# PIC18F66J60-1.net
KiCad netlist of a schematic drawn in EAGLE
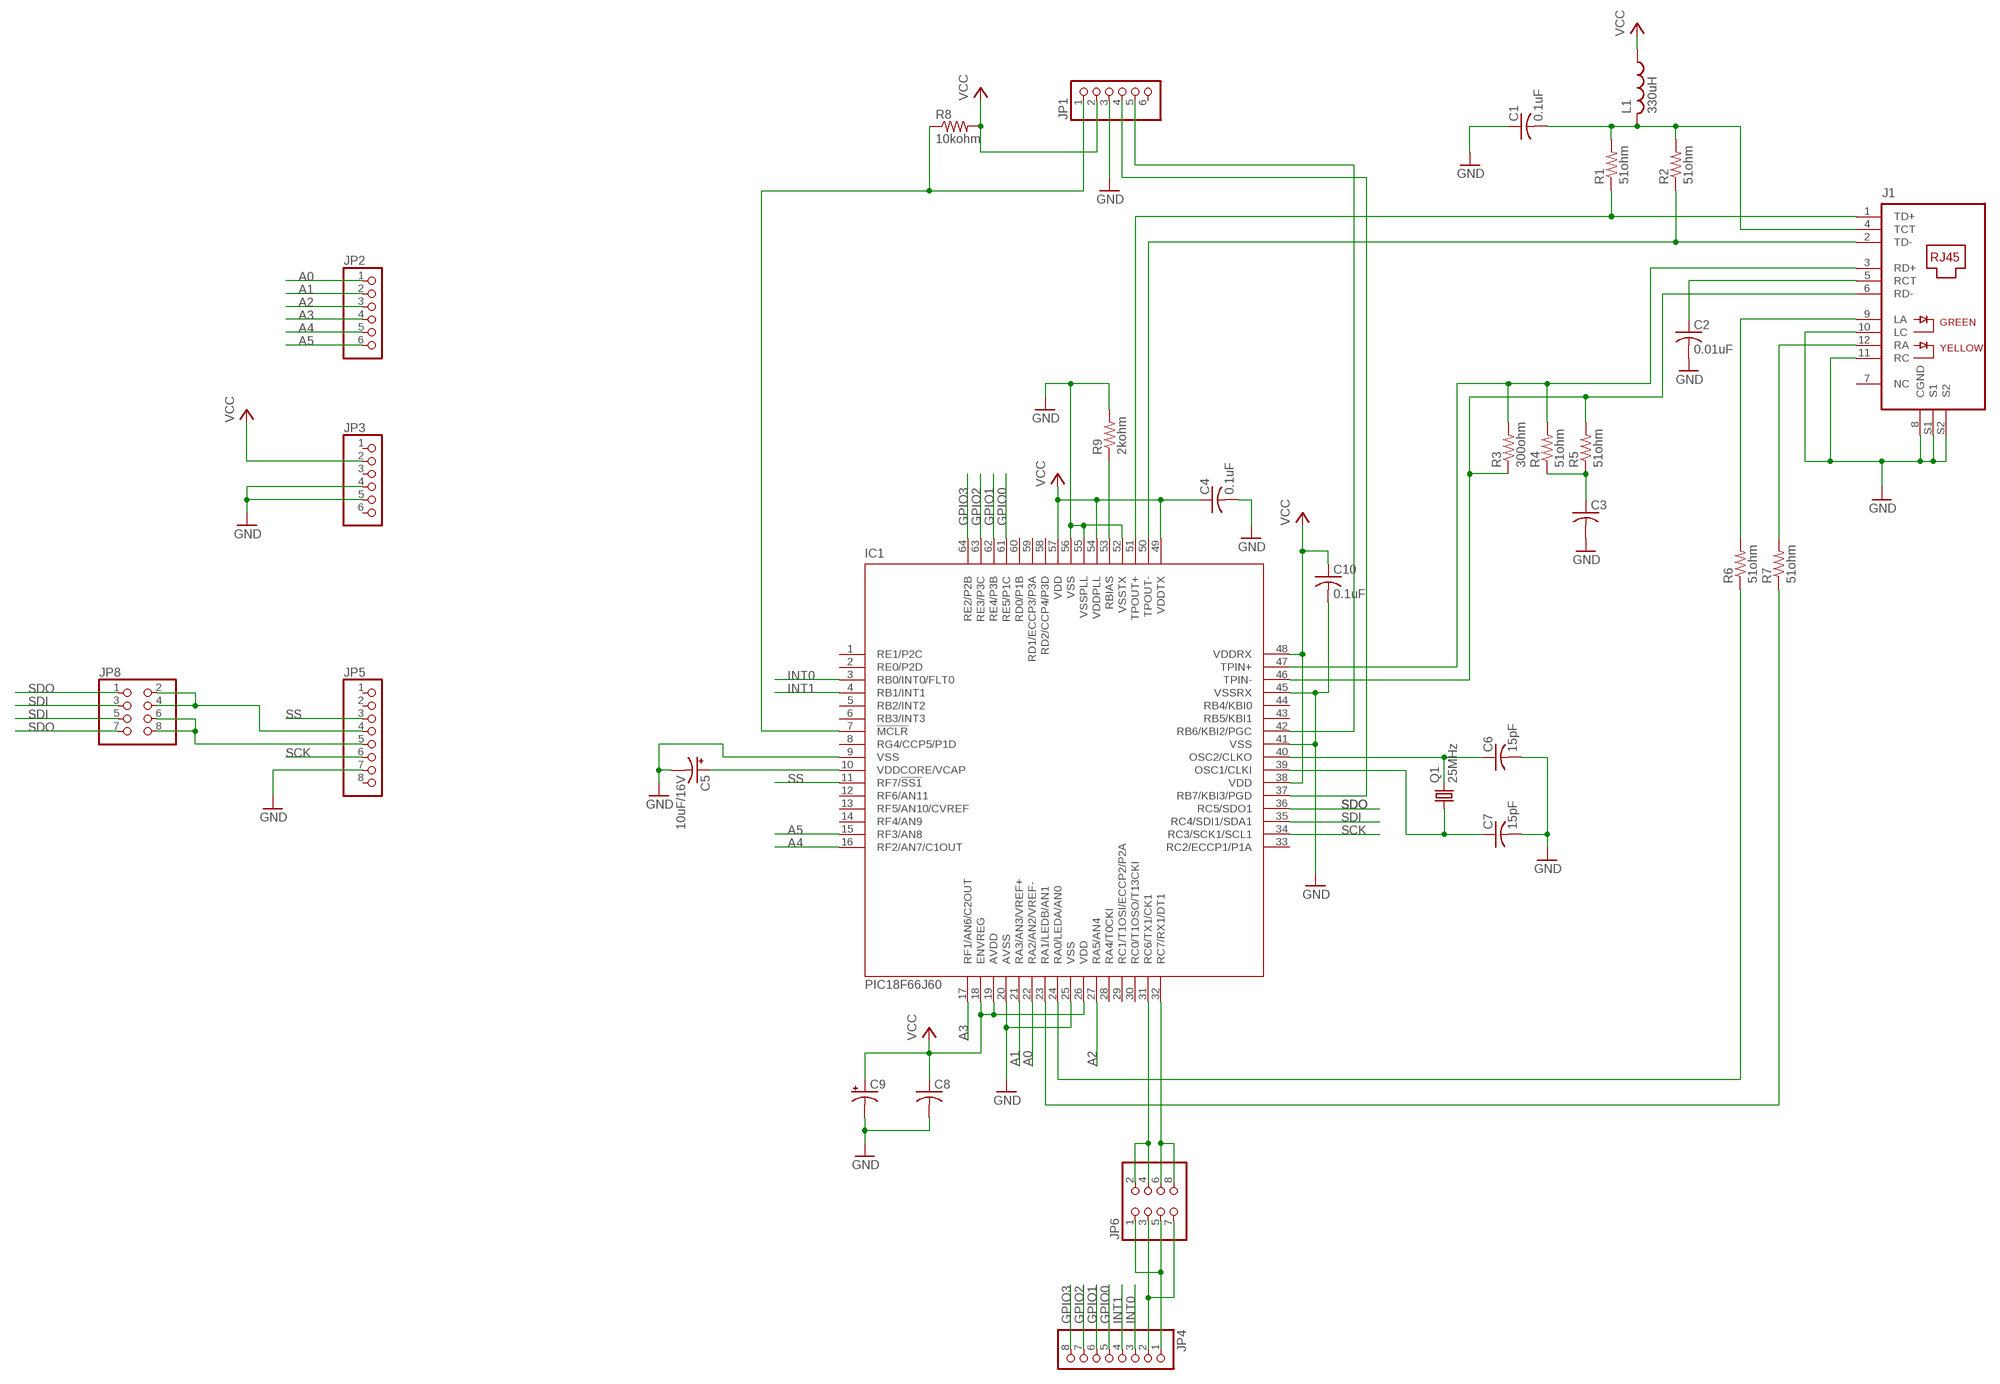
[diagram p0: schematic, sheet 1]

(export (version "E")
  (design (tool "Eeschema 10.0.6"))
  (components
    (comp (ref "C1")
      (value "0.1uF")
      (footprint "eagle-import:C025-040X050")
      (libsource (lib "eagle-import") (part "C-US025-040X050"))
    )
    (comp (ref "C2")
      (value "0.01uF")
      (footprint "eagle-import:C025-040X050")
      (libsource (lib "eagle-import") (part "C-US025-040X050"))
    )
    (comp (ref "C3")
      (value "C-US025-040X050")
      (footprint "eagle-import:C025-040X050")
      (libsource (lib "eagle-import") (part "C-US025-040X050"))
    )
    (comp (ref "C4")
      (value "0.1uF")
      (footprint "eagle-import:C025-040X050")
      (libsource (lib "eagle-import") (part "C-US025-040X050"))
    )
    (comp (ref "C5")
      (value "10uF/16V")
      (footprint "eagle-import:E2,5-7")
      (libsource (lib "eagle-import") (part "CPOL-USE2.5-7"))
    )
    (comp (ref "C6")
      (value "15pF")
      (footprint "eagle-import:C025-040X050")
      (libsource (lib "eagle-import") (part "C-US025-040X050"))
    )
    (comp (ref "C7")
      (value "15pF")
      (footprint "eagle-import:C025-040X050")
      (libsource (lib "eagle-import") (part "C-US025-040X050"))
    )
    (comp (ref "C8")
      (value "C-US025-040X050")
      (footprint "eagle-import:C025-040X050")
      (libsource (lib "eagle-import") (part "C-US025-040X050"))
    )
    (comp (ref "C9")
      (value "CPOL-USE2.5-7")
      (footprint "eagle-import:E2,5-7")
      (libsource (lib "eagle-import") (part "CPOL-USE2.5-7"))
    )
    (comp (ref "C10")
      (value "0.1uF")
      (footprint "eagle-import:C025-040X050")
      (libsource (lib "eagle-import") (part "C-US025-040X050"))
    )
    (comp (ref "IC1")
      (value "PIC18F66J60")
      (footprint "eagle-import:TQFP64-10X10")
      (fields (field (name "MPN") "PIC18F66J60-I/PT"))
      (libsource (lib "eagle-import") (part "PIC18F6J606"))
    )
    (comp (ref "J1")
      (value "J0011")
      (footprint "eagle-import:PJ-J0")
      (libsource (lib "eagle-import") (part "J0011"))
    )
    (comp (ref "JP1")
      (value "PINHD-1X6")
      (footprint "eagle-import:1X06")
      (libsource (lib "eagle-import") (part "PINHD-1X6"))
    )
    (comp (ref "JP2")
      (value "PINHD-1X6")
      (footprint "eagle-import:1X06")
      (libsource (lib "eagle-import") (part "PINHD-1X6"))
    )
    (comp (ref "JP3")
      (value "PINHD-1X6")
      (footprint "eagle-import:1X06")
      (libsource (lib "eagle-import") (part "PINHD-1X6"))
    )
    (comp (ref "JP4")
      (value "PINHD-1X8")
      (footprint "eagle-import:1X08")
      (libsource (lib "eagle-import") (part "PINHD-1X8"))
    )
    (comp (ref "JP5")
      (value "PINHD-1X8")
      (footprint "eagle-import:1X08")
      (libsource (lib "eagle-import") (part "PINHD-1X8"))
    )
    (comp (ref "JP6")
      (value "PINHD-2X4")
      (footprint "eagle-import:2X04")
      (libsource (lib "eagle-import") (part "PINHD-2X4"))
    )
    (comp (ref "JP8")
      (value "PINHD-2X4")
      (footprint "eagle-import:2X04")
      (libsource (lib "eagle-import") (part "PINHD-2X4"))
    )
    (comp (ref "L1")
      (value "330uH")
      (footprint "eagle-import:0204V")
      (libsource (lib "eagle-import") (part "L-US-01"))
    )
    (comp (ref "Q1")
      (value "25MHz")
      (footprint "eagle-import:HC49_S")
      (libsource (lib "eagle-import") (part "CRYSTALHC49S"))
    )
    (comp (ref "R1")
      (value "51ohm")
      (footprint "eagle-import:0204V")
      (libsource (lib "eagle-import") (part "R-US-01"))
    )
    (comp (ref "R2")
      (value "51ohm")
      (footprint "eagle-import:0204V")
      (libsource (lib "eagle-import") (part "R-US-01"))
    )
    (comp (ref "R3")
      (value "300ohm")
      (footprint "eagle-import:0204V")
      (libsource (lib "eagle-import") (part "R-US-01"))
    )
    (comp (ref "R4")
      (value "51ohm")
      (footprint "eagle-import:0204V")
      (libsource (lib "eagle-import") (part "R-US-01"))
    )
    (comp (ref "R5")
      (value "51ohm")
      (footprint "eagle-import:0204V")
      (libsource (lib "eagle-import") (part "R-US-01"))
    )
    (comp (ref "R6")
      (value "51ohm")
      (footprint "eagle-import:0204V")
      (libsource (lib "eagle-import") (part "R-US-01"))
    )
    (comp (ref "R7")
      (value "51ohm")
      (footprint "eagle-import:0204V")
      (libsource (lib "eagle-import") (part "R-US-01"))
    )
    (comp (ref "R8")
      (value "10kohm")
      (footprint "eagle-import:0204V")
      (libsource (lib "eagle-import") (part "R-US-01"))
    )
    (comp (ref "R9")
      (value "2kohm")
      (footprint "eagle-import:0204V")
      (libsource (lib "eagle-import") (part "R-US-01"))
    )
  )
  (nets
    (net (code "1") (name "/A0") (class "Default")
      (node (ref "IC1") (pin "22") (pinfunction "RA2/AN2/VREF-_22") (pintype "bidirectional"))
      (node (ref "JP2") (pin "1") (pinfunction "1_1") (pintype "passive"))
    )
    (net (code "2") (name "/A1") (class "Default")
      (node (ref "IC1") (pin "21") (pinfunction "RA3/AN3/VREF+_21") (pintype "bidirectional"))
      (node (ref "JP2") (pin "2") (pinfunction "2_2") (pintype "passive"))
    )
    (net (code "3") (name "/A2") (class "Default")
      (node (ref "IC1") (pin "27") (pinfunction "RA5/AN4_27") (pintype "bidirectional"))
      (node (ref "JP2") (pin "3") (pinfunction "3_3") (pintype "passive"))
    )
    (net (code "4") (name "/A3") (class "Default")
      (node (ref "IC1") (pin "17") (pinfunction "RF1/AN6/C2OUT_17") (pintype "bidirectional"))
      (node (ref "JP2") (pin "4") (pinfunction "4_4") (pintype "passive"))
    )
    (net (code "5") (name "/A4") (class "Default")
      (node (ref "IC1") (pin "16") (pinfunction "RF2/AN7/C1OUT_16") (pintype "bidirectional"))
      (node (ref "JP2") (pin "5") (pinfunction "5_5") (pintype "passive"))
    )
    (net (code "6") (name "/A5") (class "Default")
      (node (ref "IC1") (pin "15") (pinfunction "RF3/AN8_15") (pintype "bidirectional"))
      (node (ref "JP2") (pin "6") (pinfunction "6_6") (pintype "passive"))
    )
    (net (code "7") (name "/GPIO0") (class "Default")
      (node (ref "IC1") (pin "61") (pinfunction "RE5/P1C_61") (pintype "bidirectional"))
      (node (ref "JP4") (pin "5") (pinfunction "5_5") (pintype "passive"))
    )
    (net (code "8") (name "/GPIO1") (class "Default")
      (node (ref "IC1") (pin "62") (pinfunction "RE4/P3B_62") (pintype "bidirectional"))
      (node (ref "JP4") (pin "6") (pinfunction "6_6") (pintype "passive"))
    )
    (net (code "9") (name "/GPIO2") (class "Default")
      (node (ref "IC1") (pin "63") (pinfunction "RE3/P3C_63") (pintype "bidirectional"))
      (node (ref "JP4") (pin "7") (pinfunction "7_7") (pintype "passive"))
    )
    (net (code "10") (name "/GPIO3") (class "Default")
      (node (ref "IC1") (pin "64") (pinfunction "RE2/P2B_64") (pintype "bidirectional"))
      (node (ref "JP4") (pin "8") (pinfunction "8_8") (pintype "passive"))
    )
    (net (code "11") (name "/INT0") (class "Default")
      (node (ref "IC1") (pin "3") (pinfunction "RB0/INT0/FLT0_3") (pintype "bidirectional"))
      (node (ref "JP4") (pin "3") (pinfunction "3_3") (pintype "passive"))
    )
    (net (code "12") (name "/INT1") (class "Default")
      (node (ref "IC1") (pin "4") (pinfunction "RB1/INT1_4") (pintype "bidirectional"))
      (node (ref "JP4") (pin "4") (pinfunction "4_4") (pintype "passive"))
    )
    (net (code "13") (name "/SCK") (class "Default")
      (node (ref "IC1") (pin "34") (pinfunction "RC3/SCK1/SCL1_34") (pintype "bidirectional"))
      (node (ref "JP5") (pin "6") (pinfunction "6_6") (pintype "passive"))
    )
    (net (code "14") (name "/SDI") (class "Default")
      (node (ref "IC1") (pin "35") (pinfunction "RC4/SDI1/SDA1_35") (pintype "bidirectional"))
      (node (ref "JP8") (pin "3") (pinfunction "3_3") (pintype "passive"))
      (node (ref "JP8") (pin "5") (pinfunction "5_5") (pintype "passive"))
    )
    (net (code "15") (name "/SDO") (class "Default")
      (node (ref "IC1") (pin "36") (pinfunction "RC5/SDO1_36") (pintype "bidirectional"))
      (node (ref "JP8") (pin "1") (pinfunction "1_1") (pintype "passive"))
      (node (ref "JP8") (pin "7") (pinfunction "7_7") (pintype "passive"))
    )
    (net (code "16") (name "/SS") (class "Default")
      (node (ref "IC1") (pin "11") (pinfunction "RF7/~{SS1}_11") (pintype "bidirectional"))
      (node (ref "JP5") (pin "3") (pinfunction "3_3") (pintype "passive"))
    )
    (net (code "17") (name "GND") (class "Default")
      (node (ref "C1") (pin "1") (pinfunction "1_1") (pintype "passive"))
      (node (ref "C10") (pin "2") (pinfunction "2_2") (pintype "passive"))
      (node (ref "C2") (pin "2") (pinfunction "2_2") (pintype "passive"))
      (node (ref "C3") (pin "2") (pinfunction "2_2") (pintype "passive"))
      (node (ref "C4") (pin "2") (pinfunction "2_2") (pintype "passive"))
      (node (ref "C5") (pin "-") (pinfunction "-_-") (pintype "passive"))
      (node (ref "C6") (pin "2") (pinfunction "2_2") (pintype "passive"))
      (node (ref "C7") (pin "2") (pinfunction "2_2") (pintype "passive"))
      (node (ref "C8") (pin "2") (pinfunction "2_2") (pintype "passive"))
      (node (ref "C9") (pin "-") (pinfunction "-_-") (pintype "passive"))
      (node (ref "IC1") (pin "20") (pinfunction "AVSS_20") (pintype "bidirectional"))
      (node (ref "IC1") (pin "25") (pinfunction "VSS_25") (pintype "bidirectional"))
      (node (ref "IC1") (pin "41") (pinfunction "VSS_41") (pintype "bidirectional"))
      (node (ref "IC1") (pin "45") (pinfunction "VSSRX_45") (pintype "bidirectional"))
      (node (ref "IC1") (pin "52") (pinfunction "VSSTX_52") (pintype "bidirectional"))
      (node (ref "IC1") (pin "55") (pinfunction "VSSPLL_55") (pintype "bidirectional"))
      (node (ref "IC1") (pin "56") (pinfunction "VSS_56") (pintype "bidirectional"))
      (node (ref "IC1") (pin "9") (pinfunction "VSS_9") (pintype "bidirectional"))
      (node (ref "J1") (pin "10") (pinfunction "LC_10") (pintype "passive"))
      (node (ref "J1") (pin "11") (pinfunction "RC_11") (pintype "passive"))
      (node (ref "J1") (pin "8") (pinfunction "CGND_8") (pintype "passive"))
      (node (ref "J1") (pin "S1") (pinfunction "S1_S1") (pintype "passive"))
      (node (ref "J1") (pin "S2") (pinfunction "S2_S2") (pintype "passive"))
      (node (ref "JP1") (pin "3") (pinfunction "3_3") (pintype "passive"))
      (node (ref "JP3") (pin "4") (pinfunction "4_4") (pintype "passive"))
      (node (ref "JP3") (pin "5") (pinfunction "5_5") (pintype "passive"))
      (node (ref "JP5") (pin "7") (pinfunction "7_7") (pintype "passive"))
      (node (ref "R9") (pin "2") (pinfunction "2_2") (pintype "passive"))
    )
    (net (code "18") (name "Net-(C3-Pad1)") (class "Default")
      (node (ref "C3") (pin "1") (pinfunction "1_1") (pintype "passive"))
      (node (ref "R4") (pin "1") (pinfunction "1_1") (pintype "passive"))
      (node (ref "R5") (pin "1") (pinfunction "1_1") (pintype "passive"))
    )
    (net (code "19") (name "Net-(IC1-OSC1{slash}CLKI)") (class "Default")
      (node (ref "C7") (pin "1") (pinfunction "1_1") (pintype "passive"))
      (node (ref "IC1") (pin "39") (pinfunction "OSC1/CLKI_39") (pintype "bidirectional"))
      (node (ref "Q1") (pin "1") (pinfunction "1_1") (pintype "passive"))
    )
    (net (code "20") (name "Net-(IC1-OSC2{slash}CLKO)") (class "Default")
      (node (ref "C6") (pin "1") (pinfunction "1_1") (pintype "passive"))
      (node (ref "IC1") (pin "40") (pinfunction "OSC2/CLKO_40") (pintype "bidirectional"))
      (node (ref "Q1") (pin "2") (pinfunction "2_2") (pintype "passive"))
    )
    (net (code "21") (name "Net-(IC1-RA0{slash}LEDA{slash}AN0)") (class "Default")
      (node (ref "IC1") (pin "24") (pinfunction "RA0/LEDA/AN0_24") (pintype "bidirectional"))
      (node (ref "R6") (pin "1") (pinfunction "1_1") (pintype "passive"))
    )
    (net (code "22") (name "Net-(IC1-RA1{slash}LEDB{slash}AN1)") (class "Default")
      (node (ref "IC1") (pin "23") (pinfunction "RA1/LEDB/AN1_23") (pintype "bidirectional"))
      (node (ref "R7") (pin "1") (pinfunction "1_1") (pintype "passive"))
    )
    (net (code "23") (name "Net-(IC1-RB6{slash}KBI2{slash}PGC)") (class "Default")
      (node (ref "IC1") (pin "42") (pinfunction "RB6/KBI2/PGC_42") (pintype "bidirectional"))
      (node (ref "JP1") (pin "5") (pinfunction "5_5") (pintype "passive"))
    )
    (net (code "24") (name "Net-(IC1-RB7{slash}KBI3{slash}PGD)") (class "Default")
      (node (ref "IC1") (pin "37") (pinfunction "RB7/KBI3/PGD_37") (pintype "bidirectional"))
      (node (ref "JP1") (pin "4") (pinfunction "4_4") (pintype "passive"))
    )
    (net (code "25") (name "Net-(IC1-RBIAS)") (class "Default")
      (node (ref "IC1") (pin "53") (pinfunction "RBIAS_53") (pintype "bidirectional"))
      (node (ref "R9") (pin "1") (pinfunction "1_1") (pintype "passive"))
    )
    (net (code "26") (name "Net-(IC1-RC6{slash}TX1{slash}CK1)") (class "Default")
      (node (ref "IC1") (pin "31") (pinfunction "RC6/TX1/CK1_31") (pintype "bidirectional"))
      (node (ref "JP6") (pin "2") (pinfunction "2_2") (pintype "passive"))
      (node (ref "JP6") (pin "4") (pinfunction "4_4") (pintype "passive"))
    )
    (net (code "27") (name "Net-(IC1-RC7{slash}RX1{slash}DT1)") (class "Default")
      (node (ref "IC1") (pin "32") (pinfunction "RC7/RX1/DT1_32") (pintype "bidirectional"))
      (node (ref "JP6") (pin "6") (pinfunction "6_6") (pintype "passive"))
      (node (ref "JP6") (pin "8") (pinfunction "8_8") (pintype "passive"))
    )
    (net (code "28") (name "Net-(IC1-TPIN+)") (class "Default")
      (node (ref "IC1") (pin "47") (pinfunction "TPIN+_47") (pintype "bidirectional"))
      (node (ref "J1") (pin "3") (pinfunction "RD+_3") (pintype "bidirectional"))
      (node (ref "R3") (pin "2") (pinfunction "2_2") (pintype "passive"))
      (node (ref "R4") (pin "2") (pinfunction "2_2") (pintype "passive"))
    )
    (net (code "29") (name "Net-(IC1-TPIN-)") (class "Default")
      (node (ref "IC1") (pin "46") (pinfunction "TPIN-_46") (pintype "bidirectional"))
      (node (ref "J1") (pin "6") (pinfunction "RD-_6") (pintype "bidirectional"))
      (node (ref "R3") (pin "1") (pinfunction "1_1") (pintype "passive"))
      (node (ref "R5") (pin "2") (pinfunction "2_2") (pintype "passive"))
    )
    (net (code "30") (name "Net-(IC1-TPOUT+)") (class "Default")
      (node (ref "IC1") (pin "51") (pinfunction "TPOUT+_51") (pintype "bidirectional"))
      (node (ref "J1") (pin "1") (pinfunction "TD+_1") (pintype "bidirectional"))
      (node (ref "R1") (pin "1") (pinfunction "1_1") (pintype "passive"))
    )
    (net (code "31") (name "Net-(IC1-TPOUT-)") (class "Default")
      (node (ref "IC1") (pin "50") (pinfunction "TPOUT-_50") (pintype "bidirectional"))
      (node (ref "J1") (pin "2") (pinfunction "TD-_2") (pintype "bidirectional"))
      (node (ref "R2") (pin "1") (pinfunction "1_1") (pintype "passive"))
    )
    (net (code "32") (name "Net-(IC1-VDDCORE{slash}VCAP)") (class "Default")
      (node (ref "C5") (pin "+") (pinfunction "+_+") (pintype "passive"))
      (node (ref "IC1") (pin "10") (pinfunction "VDDCORE/VCAP_10") (pintype "bidirectional"))
    )
    (net (code "33") (name "Net-(IC1-~{MCLR})") (class "Default")
      (node (ref "IC1") (pin "7") (pinfunction "~{MCLR}_7") (pintype "bidirectional"))
      (node (ref "JP1") (pin "1") (pinfunction "1_1") (pintype "passive"))
      (node (ref "R8") (pin "1") (pinfunction "1_1") (pintype "passive"))
    )
    (net (code "34") (name "Net-(J1-LA)") (class "Default")
      (node (ref "J1") (pin "9") (pinfunction "LA_9") (pintype "passive"))
      (node (ref "R6") (pin "2") (pinfunction "2_2") (pintype "passive"))
    )
    (net (code "35") (name "Net-(J1-RA)") (class "Default")
      (node (ref "J1") (pin "12") (pinfunction "RA_12") (pintype "passive"))
      (node (ref "R7") (pin "2") (pinfunction "2_2") (pintype "passive"))
    )
    (net (code "36") (name "Net-(J1-RCT)") (class "Default")
      (node (ref "C2") (pin "1") (pinfunction "1_1") (pintype "passive"))
      (node (ref "J1") (pin "5") (pinfunction "RCT_5") (pintype "bidirectional"))
    )
    (net (code "37") (name "Net-(J1-TCT)") (class "Default")
      (node (ref "C1") (pin "2") (pinfunction "2_2") (pintype "passive"))
      (node (ref "J1") (pin "4") (pinfunction "TCT_4") (pintype "bidirectional"))
      (node (ref "L1") (pin "2") (pinfunction "2_2") (pintype "passive"))
      (node (ref "R1") (pin "2") (pinfunction "2_2") (pintype "passive"))
      (node (ref "R2") (pin "2") (pinfunction "2_2") (pintype "passive"))
    )
    (net (code "38") (name "Net-(JP4-Pad1)") (class "Default")
      (node (ref "JP4") (pin "1") (pinfunction "1_1") (pintype "passive"))
      (node (ref "JP6") (pin "1") (pinfunction "1_1") (pintype "passive"))
      (node (ref "JP6") (pin "5") (pinfunction "5_5") (pintype "passive"))
    )
    (net (code "39") (name "Net-(JP4-Pad2)") (class "Default")
      (node (ref "JP4") (pin "2") (pinfunction "2_2") (pintype "passive"))
      (node (ref "JP6") (pin "3") (pinfunction "3_3") (pintype "passive"))
      (node (ref "JP6") (pin "7") (pinfunction "7_7") (pintype "passive"))
    )
    (net (code "40") (name "Net-(JP5-Pad4)") (class "Default")
      (node (ref "JP5") (pin "4") (pinfunction "4_4") (pintype "passive"))
      (node (ref "JP8") (pin "2") (pinfunction "2_2") (pintype "passive"))
      (node (ref "JP8") (pin "4") (pinfunction "4_4") (pintype "passive"))
    )
    (net (code "41") (name "Net-(JP5-Pad5)") (class "Default")
      (node (ref "JP5") (pin "5") (pinfunction "5_5") (pintype "passive"))
      (node (ref "JP8") (pin "6") (pinfunction "6_6") (pintype "passive"))
      (node (ref "JP8") (pin "8") (pinfunction "8_8") (pintype "passive"))
    )
    (net (code "42") (name "VCC") (class "Default")
      (node (ref "C10") (pin "1") (pinfunction "1_1") (pintype "passive"))
      (node (ref "C4") (pin "1") (pinfunction "1_1") (pintype "passive"))
      (node (ref "C8") (pin "1") (pinfunction "1_1") (pintype "passive"))
      (node (ref "C9") (pin "+") (pinfunction "+_+") (pintype "passive"))
      (node (ref "IC1") (pin "18") (pinfunction "ENVREG_18") (pintype "bidirectional"))
      (node (ref "IC1") (pin "19") (pinfunction "AVDD_19") (pintype "bidirectional"))
      (node (ref "IC1") (pin "26") (pinfunction "VDD_26") (pintype "bidirectional"))
      (node (ref "IC1") (pin "38") (pinfunction "VDD_38") (pintype "bidirectional"))
      (node (ref "IC1") (pin "48") (pinfunction "VDDRX_48") (pintype "bidirectional"))
      (node (ref "IC1") (pin "49") (pinfunction "VDDTX_49") (pintype "bidirectional"))
      (node (ref "IC1") (pin "54") (pinfunction "VDDPLL_54") (pintype "bidirectional"))
      (node (ref "IC1") (pin "57") (pinfunction "VDD_57") (pintype "bidirectional"))
      (node (ref "JP1") (pin "2") (pinfunction "2_2") (pintype "passive"))
      (node (ref "JP3") (pin "2") (pinfunction "2_2") (pintype "passive"))
      (node (ref "L1") (pin "1") (pinfunction "1_1") (pintype "passive"))
      (node (ref "R8") (pin "2") (pinfunction "2_2") (pintype "passive"))
    )
    (net (code "43") (name "unconnected-(IC1-RA4{slash}T0CKI-Pad28)") (class "Default")
      (node (ref "IC1") (pin "28") (pinfunction "RA4/T0CKI_28") (pintype "bidirectional"))
    )
    (net (code "44") (name "unconnected-(IC1-RB2{slash}INT2-Pad5)") (class "Default")
      (node (ref "IC1") (pin "5") (pinfunction "RB2/INT2_5") (pintype "bidirectional"))
    )
    (net (code "45") (name "unconnected-(IC1-RB3{slash}INT3-Pad6)") (class "Default")
      (node (ref "IC1") (pin "6") (pinfunction "RB3/INT3_6") (pintype "bidirectional"))
    )
    (net (code "46") (name "unconnected-(IC1-RB4{slash}KBI0-Pad44)") (class "Default")
      (node (ref "IC1") (pin "44") (pinfunction "RB4/KBI0_44") (pintype "bidirectional"))
    )
    (net (code "47") (name "unconnected-(IC1-RB5{slash}KBI1-Pad43)") (class "Default")
      (node (ref "IC1") (pin "43") (pinfunction "RB5/KBI1_43") (pintype "bidirectional"))
    )
    (net (code "48") (name "unconnected-(IC1-RC0{slash}T1OSO{slash}T13CKI-Pad30)") (class "Default")
      (node (ref "IC1") (pin "30") (pinfunction "RC0/T1OSO/T13CKI_30") (pintype "bidirectional"))
    )
    (net (code "49") (name "unconnected-(IC1-RC1{slash}T1OSI{slash}ECCP2{slash}P2A-Pad29)") (class "Default")
      (node (ref "IC1") (pin "29") (pinfunction "RC1/T1OSI/ECCP2/P2A_29") (pintype "bidirectional"))
    )
    (net (code "50") (name "unconnected-(IC1-RC2{slash}ECCP1{slash}P1A-Pad33)") (class "Default")
      (node (ref "IC1") (pin "33") (pinfunction "RC2/ECCP1/P1A_33") (pintype "bidirectional"))
    )
    (net (code "51") (name "unconnected-(IC1-RD0{slash}P1B-Pad60)") (class "Default")
      (node (ref "IC1") (pin "60") (pinfunction "RD0/P1B_60") (pintype "bidirectional"))
    )
    (net (code "52") (name "unconnected-(IC1-RD1{slash}ECCP3{slash}P3A-Pad59)") (class "Default")
      (node (ref "IC1") (pin "59") (pinfunction "RD1/ECCP3/P3A_59") (pintype "bidirectional"))
    )
    (net (code "53") (name "unconnected-(IC1-RD2{slash}CCP4{slash}P3D-Pad58)") (class "Default")
      (node (ref "IC1") (pin "58") (pinfunction "RD2/CCP4/P3D_58") (pintype "bidirectional"))
    )
    (net (code "54") (name "unconnected-(IC1-RE0{slash}P2D-Pad2)") (class "Default")
      (node (ref "IC1") (pin "2") (pinfunction "RE0/P2D_2") (pintype "bidirectional"))
    )
    (net (code "55") (name "unconnected-(IC1-RE1{slash}P2C-Pad1)") (class "Default")
      (node (ref "IC1") (pin "1") (pinfunction "RE1/P2C_1") (pintype "bidirectional"))
    )
    (net (code "56") (name "unconnected-(IC1-RF4{slash}AN9-Pad14)") (class "Default")
      (node (ref "IC1") (pin "14") (pinfunction "RF4/AN9_14") (pintype "bidirectional"))
    )
    (net (code "57") (name "unconnected-(IC1-RF5{slash}AN10{slash}CVREF-Pad13)") (class "Default")
      (node (ref "IC1") (pin "13") (pinfunction "RF5/AN10/CVREF_13") (pintype "bidirectional"))
    )
    (net (code "58") (name "unconnected-(IC1-RF6{slash}AN11-Pad12)") (class "Default")
      (node (ref "IC1") (pin "12") (pinfunction "RF6/AN11_12") (pintype "bidirectional"))
    )
    (net (code "59") (name "unconnected-(IC1-RG4{slash}CCP5{slash}P1D-Pad8)") (class "Default")
      (node (ref "IC1") (pin "8") (pinfunction "RG4/CCP5/P1D_8") (pintype "bidirectional"))
    )
    (net (code "60") (name "unconnected-(J1-NC-Pad7)") (class "Default")
      (node (ref "J1") (pin "7") (pinfunction "NC_7") (pintype "no_connect"))
    )
    (net (code "61") (name "unconnected-(JP1-Pad6)") (class "Default")
      (node (ref "JP1") (pin "6") (pinfunction "6_6") (pintype "passive"))
    )
    (net (code "62") (name "unconnected-(JP3-Pad1)") (class "Default")
      (node (ref "JP3") (pin "1") (pinfunction "1_1") (pintype "passive"))
    )
    (net (code "63") (name "unconnected-(JP3-Pad3)") (class "Default")
      (node (ref "JP3") (pin "3") (pinfunction "3_3") (pintype "passive"))
    )
    (net (code "64") (name "unconnected-(JP3-Pad6)") (class "Default")
      (node (ref "JP3") (pin "6") (pinfunction "6_6") (pintype "passive"))
    )
    (net (code "65") (name "unconnected-(JP5-Pad1)") (class "Default")
      (node (ref "JP5") (pin "1") (pinfunction "1_1") (pintype "passive"))
    )
    (net (code "66") (name "unconnected-(JP5-Pad2)") (class "Default")
      (node (ref "JP5") (pin "2") (pinfunction "2_2") (pintype "passive"))
    )
    (net (code "67") (name "unconnected-(JP5-Pad8)") (class "Default")
      (node (ref "JP5") (pin "8") (pinfunction "8_8") (pintype "passive"))
    )
  )
)
